# CKLink_Lite.net
KiCad netlist of a schematic drawn in Altium Designer
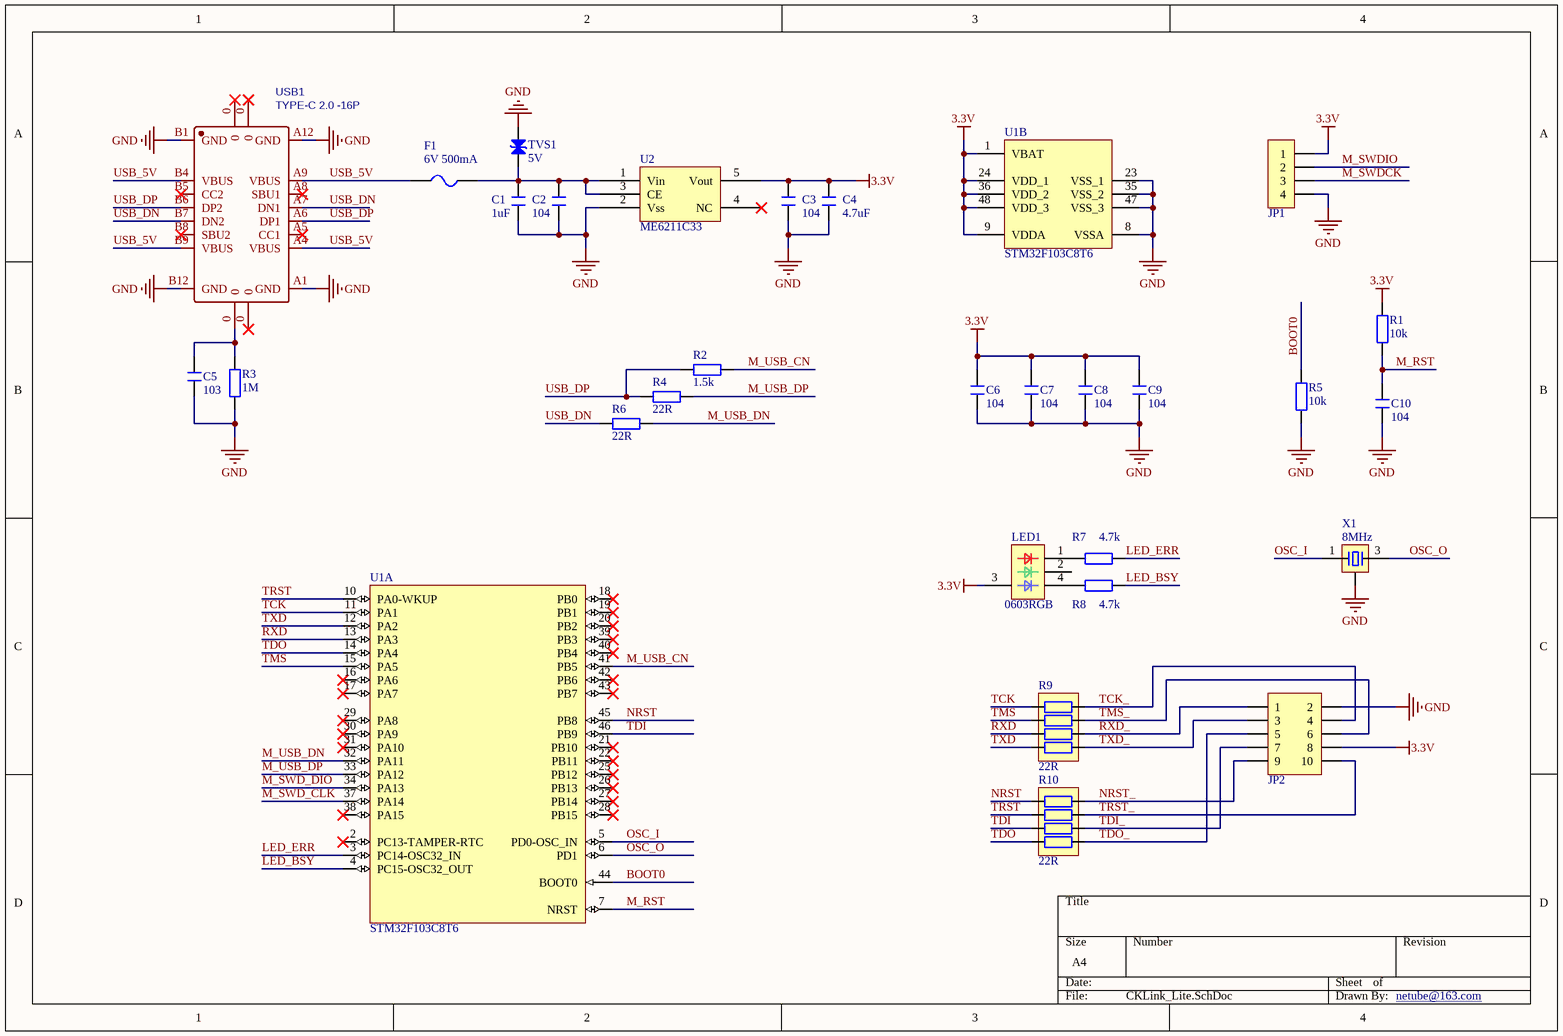
[diagram p0: CKLink_Lite.SchDoc]

(export (version "E")
  (design (tool "Eeschema 10.0.6"))
  (components
    (comp (ref "C1")
      (value "1uF")
      (footprint "C 0603_L")
      (description "贴片电容")
      (libsource (lib "0.1 - 电阻-电容-电感") (part "C"))
    )
    (comp (ref "C2")
      (value "104")
      (footprint "C 0603_L")
      (description "贴片电容")
      (libsource (lib "0.1 - 电阻-电容-电感") (part "C"))
    )
    (comp (ref "C3")
      (value "104")
      (footprint "C 0603_L")
      (description "贴片电容")
      (libsource (lib "0.1 - 电阻-电容-电感") (part "C"))
    )
    (comp (ref "C4")
      (value "4.7uF")
      (footprint "C 0603_L")
      (description "贴片电容")
      (libsource (lib "0.1 - 电阻-电容-电感") (part "C"))
    )
    (comp (ref "C5")
      (value "103")
      (footprint "C 0603_L")
      (description "贴片电容")
      (libsource (lib "0.1 - 电阻-电容-电感") (part "C"))
    )
    (comp (ref "C6")
      (value "104")
      (footprint "C 0603_L")
      (description "贴片电容")
      (libsource (lib "0.1 - 电阻-电容-电感") (part "C"))
    )
    (comp (ref "C7")
      (value "104")
      (footprint "C 0603_L")
      (description "贴片电容")
      (libsource (lib "0.1 - 电阻-电容-电感") (part "C"))
    )
    (comp (ref "C8")
      (value "104")
      (footprint "C 0603_L")
      (description "贴片电容")
      (libsource (lib "0.1 - 电阻-电容-电感") (part "C"))
    )
    (comp (ref "C9")
      (value "104")
      (footprint "C 0603_L")
      (description "贴片电容")
      (libsource (lib "0.1 - 电阻-电容-电感") (part "C"))
    )
    (comp (ref "C10")
      (value "104")
      (footprint "C 0603_L")
      (description "贴片电容")
      (libsource (lib "0.1 - 电阻-电容-电感") (part "C"))
    )
    (comp (ref "F1")
      (value "6V 500mA")
      (footprint "FU 0805")
      (description "贴片保险丝")
      (fields (field (name "版权归属") "封装库来自淘宝卖家 ID：黄晶宝石"))
      (libsource (lib "0.5 - 保险丝-晶振-光耦") (part "FU"))
    )
    (comp (ref "JP1")
      (value "HDR-1X4")
      (footprint "HDR2.54-LI-4P")
      (description "4P接插件")
      (fields (field (name "版权归属") "封装库来自淘宝 ID：黄晶宝石"))
      (libsource (lib "5.4 - 接插件-脚距2.54 (100mil) ") (part "Header 4"))
    )
    (comp (ref "JP2")
      (value "Header 5X2")
      (footprint "CHE2*5")
      (description "5*2P接插件")
      (fields (field (name "版权归属") "封装库来自淘宝 ID：黄晶宝石"))
      (libsource (lib "5.4 - 接插件-脚距2.54 (100mil) ") (part "Header 5X2"))
    )
    (comp (ref "LED1")
      (value "0603RGB")
      (footprint "0603RGB")
      (libsource (lib "0.3 - LED发光二极管") (part "0603RGB"))
    )
    (comp (ref "R1")
      (value "10k")
      (footprint "R 0603_L")
      (description "贴片电阻")
      (libsource (lib "0.1 - 电阻-电容-电感") (part "R"))
    )
    (comp (ref "R2")
      (value "1.5k")
      (footprint "R 0603_L")
      (description "贴片电阻")
      (libsource (lib "0.1 - 电阻-电容-电感") (part "R"))
    )
    (comp (ref "R3")
      (value "1M")
      (footprint "R 0603_L")
      (description "贴片电阻")
      (libsource (lib "0.1 - 电阻-电容-电感") (part "R"))
    )
    (comp (ref "R4")
      (value "22R")
      (footprint "R 0603_L")
      (description "贴片电阻")
      (libsource (lib "0.1 - 电阻-电容-电感") (part "R"))
    )
    (comp (ref "R5")
      (value "10k")
      (footprint "R 0603_L")
      (description "贴片电阻")
      (libsource (lib "0.1 - 电阻-电容-电感") (part "R"))
    )
    (comp (ref "R6")
      (value "22R")
      (footprint "R 0603_L")
      (description "贴片电阻")
      (libsource (lib "0.1 - 电阻-电容-电感") (part "R"))
    )
    (comp (ref "R7")
      (value "4.7k")
      (footprint "R 0603_L")
      (description "贴片电阻")
      (libsource (lib "0.1 - 电阻-电容-电感") (part "R"))
    )
    (comp (ref "R8")
      (value "4.7k")
      (footprint "R 0603_L")
      (description "贴片电阻")
      (libsource (lib "0.1 - 电阻-电容-电感") (part "R"))
    )
    (comp (ref "R9")
      (value "22R")
      (footprint "RCA-8P4R-0603")
      (description "贴片排阻")
      (libsource (lib "") (part "R-8P4R_1"))
    )
    (comp (ref "R10")
      (value "22R")
      (footprint "RCA-8P4R-0603")
      (description "贴片排阻")
      (libsource (lib "0.1 - 电阻-电容-电感") (part "R-8P4R"))
    )
    (comp (ref "TVS1")
      (value "5V")
      (footprint "SOD-323")
      (description "TVS保护")
      (libsource (lib "0.2 - 二极管-整流桥") (part "TVS"))
    )
    (comp (ref "U1")
      (value "STM32F103C8T6")
      (footprint "LQFP48_L")
      (libsource (lib "2.3 - STM32 F1系列单片机") (part "STM32F103C8T6"))
    )
    (comp (ref "U2")
      (value "ME6211C33")
      (footprint "SOT23-5N")
      (description "3.3V 500mA 低压差线性稳压器")
      (libsource (lib "1.1 - 电源类芯片") (part "ME6211C33"))
    )
    (comp (ref "USB1")
      (value "TYPE-C 2.0 -16P")
      (footprint "USB-TYPE-C_16PIN-MALE-TYPE-C-31-M-12")
      (description "USB2.0 Type-C 母座 16Pin")
      (libsource (lib "0.8 - 以太网-音频-USB插座") (part "USB2.0 Type-C 16Pin母座"))
    )
    (comp (ref "X1")
      (value "8MHz")
      (footprint "CSTCE 3pin")
      (description "3脚无源晶振")
      (fields (field (name "版权归属") "封装库来自淘宝卖家 ID：黄晶宝石"))
      (libsource (lib "0.5 - 保险丝-晶振-光耦") (part "XTAL-3P"))
    )
  )
  (nets
    (net (code "1") (name "/BOOT0") (class "Default")
      (node (ref "R5") (pin "2") (pinfunction "2_2") (pintype "passive"))
      (node (ref "U1") (pin "44") (pinfunction "BOOT0_44") (pintype "input"))
    )
    (net (code "2") (name "/LED_BSY") (class "Default")
      (node (ref "R8") (pin "1") (pinfunction "1_1") (pintype "passive"))
      (node (ref "U1") (pin "4") (pinfunction "PC15-OSC32_OUT_4") (pintype "bidirectional"))
    )
    (net (code "3") (name "/LED_ERR") (class "Default")
      (node (ref "R7") (pin "1") (pinfunction "1_1") (pintype "passive"))
      (node (ref "U1") (pin "3") (pinfunction "PC14-OSC32_IN_3") (pintype "bidirectional"))
    )
    (net (code "4") (name "/M_RST") (class "Default")
      (node (ref "C10") (pin "2") (pinfunction "2_2") (pintype "passive"))
      (node (ref "R1") (pin "1") (pinfunction "1_1") (pintype "passive"))
      (node (ref "U1") (pin "7") (pinfunction "NRST_7") (pintype "bidirectional"))
    )
    (net (code "5") (name "/M_SWDCK") (class "Default")
      (node (ref "JP1") (pin "3") (pinfunction "3_3") (pintype "passive"))
    )
    (net (code "6") (name "/M_SWDIO") (class "Default")
      (node (ref "JP1") (pin "2") (pinfunction "2_2") (pintype "passive"))
    )
    (net (code "7") (name "/M_SWD_CLK") (class "Default")
      (node (ref "U1") (pin "37") (pinfunction "PA14_37") (pintype "bidirectional"))
    )
    (net (code "8") (name "/M_SWD_DIO") (class "Default")
      (node (ref "U1") (pin "34") (pinfunction "PA13_34") (pintype "bidirectional"))
    )
    (net (code "9") (name "/M_USB_CN") (class "Default")
      (node (ref "R2") (pin "1") (pinfunction "1_1") (pintype "passive"))
      (node (ref "U1") (pin "41") (pinfunction "PB5_41") (pintype "bidirectional"))
    )
    (net (code "10") (name "/M_USB_DN") (class "Default")
      (node (ref "R6") (pin "1") (pinfunction "1_1") (pintype "passive"))
      (node (ref "U1") (pin "32") (pinfunction "PA11_32") (pintype "bidirectional"))
    )
    (net (code "11") (name "/M_USB_DP") (class "Default")
      (node (ref "R4") (pin "1") (pinfunction "1_1") (pintype "passive"))
      (node (ref "U1") (pin "33") (pinfunction "PA12_33") (pintype "bidirectional"))
    )
    (net (code "12") (name "/NRST") (class "Default")
      (node (ref "R10") (pin "4") (pinfunction "4_4") (pintype "passive"))
      (node (ref "U1") (pin "45") (pinfunction "PB8_45") (pintype "bidirectional"))
    )
    (net (code "13") (name "/NRST_") (class "Default")
      (node (ref "JP2") (pin "9") (pinfunction "9_9") (pintype "passive"))
      (node (ref "R10") (pin "5") (pinfunction "5_5") (pintype "passive"))
    )
    (net (code "14") (name "/OSC_I") (class "Default")
      (node (ref "U1") (pin "5") (pinfunction "PD0-OSC_IN_5") (pintype "bidirectional"))
      (node (ref "X1") (pin "1") (pinfunction "1_1") (pintype "passive"))
    )
    (net (code "15") (name "/OSC_O") (class "Default")
      (node (ref "U1") (pin "6") (pinfunction "PD1_6") (pintype "bidirectional"))
      (node (ref "X1") (pin "3") (pinfunction "3_3") (pintype "passive"))
    )
    (net (code "16") (name "/RXD") (class "Default")
      (node (ref "R9") (pin "3") (pinfunction "3_3") (pintype "passive"))
      (node (ref "U1") (pin "13") (pinfunction "PA3_13") (pintype "bidirectional"))
    )
    (net (code "17") (name "/RXD_") (class "Default")
      (node (ref "JP2") (pin "1") (pinfunction "1_1") (pintype "passive"))
      (node (ref "R9") (pin "6") (pinfunction "6_6") (pintype "passive"))
    )
    (net (code "18") (name "/TCK") (class "Default")
      (node (ref "R9") (pin "1") (pinfunction "1_1") (pintype "passive"))
      (node (ref "U1") (pin "11") (pinfunction "PA1_11") (pintype "bidirectional"))
    )
    (net (code "19") (name "/TCK_") (class "Default")
      (node (ref "JP2") (pin "4") (pinfunction "4_4") (pintype "passive"))
      (node (ref "R9") (pin "8") (pinfunction "8_8") (pintype "passive"))
    )
    (net (code "20") (name "/TDI") (class "Default")
      (node (ref "R10") (pin "2") (pinfunction "2_2") (pintype "passive"))
      (node (ref "U1") (pin "46") (pinfunction "PB9_46") (pintype "bidirectional"))
    )
    (net (code "21") (name "/TDI_") (class "Default")
      (node (ref "JP2") (pin "7") (pinfunction "7_7") (pintype "passive"))
      (node (ref "R10") (pin "7") (pinfunction "7_7") (pintype "passive"))
    )
    (net (code "22") (name "/TDO") (class "Default")
      (node (ref "R10") (pin "1") (pinfunction "1_1") (pintype "passive"))
      (node (ref "U1") (pin "14") (pinfunction "PA4_14") (pintype "bidirectional"))
    )
    (net (code "23") (name "/TDO_") (class "Default")
      (node (ref "JP2") (pin "5") (pinfunction "5_5") (pintype "passive"))
      (node (ref "R10") (pin "8") (pinfunction "8_8") (pintype "passive"))
    )
    (net (code "24") (name "/TMS") (class "Default")
      (node (ref "R9") (pin "2") (pinfunction "2_2") (pintype "passive"))
      (node (ref "U1") (pin "15") (pinfunction "PA5_15") (pintype "bidirectional"))
    )
    (net (code "25") (name "/TMS_") (class "Default")
      (node (ref "JP2") (pin "6") (pinfunction "6_6") (pintype "passive"))
      (node (ref "R9") (pin "7") (pinfunction "7_7") (pintype "passive"))
    )
    (net (code "26") (name "/TRST") (class "Default")
      (node (ref "R10") (pin "3") (pinfunction "3_3") (pintype "passive"))
      (node (ref "U1") (pin "10") (pinfunction "PA0-WKUP_10") (pintype "bidirectional"))
    )
    (net (code "27") (name "/TRST_") (class "Default")
      (node (ref "JP2") (pin "10") (pinfunction "10_10") (pintype "passive"))
      (node (ref "R10") (pin "6") (pinfunction "6_6") (pintype "passive"))
    )
    (net (code "28") (name "/TXD") (class "Default")
      (node (ref "R9") (pin "4") (pinfunction "4_4") (pintype "passive"))
      (node (ref "U1") (pin "12") (pinfunction "PA2_12") (pintype "bidirectional"))
    )
    (net (code "29") (name "/TXD_") (class "Default")
      (node (ref "JP2") (pin "3") (pinfunction "3_3") (pintype "passive"))
      (node (ref "R9") (pin "5") (pinfunction "5_5") (pintype "passive"))
    )
    (net (code "30") (name "/USB_5V") (class "Default")
      (node (ref "F1") (pin "1") (pinfunction "1_1") (pintype "passive"))
      (node (ref "USB1") (pin "A4") (pinfunction "VBUS_A4") (pintype "passive"))
      (node (ref "USB1") (pin "A9") (pinfunction "VBUS_A9") (pintype "passive"))
      (node (ref "USB1") (pin "B4") (pinfunction "VBUS_B4") (pintype "passive"))
      (node (ref "USB1") (pin "B9") (pinfunction "VBUS_B9") (pintype "passive"))
    )
    (net (code "31") (name "/USB_DN") (class "Default")
      (node (ref "R6") (pin "2") (pinfunction "2_2") (pintype "passive"))
      (node (ref "USB1") (pin "A7") (pinfunction "DN1_A7") (pintype "passive"))
      (node (ref "USB1") (pin "B7") (pinfunction "DN2_B7") (pintype "passive"))
    )
    (net (code "32") (name "/USB_DP") (class "Default")
      (node (ref "R2") (pin "2") (pinfunction "2_2") (pintype "passive"))
      (node (ref "R4") (pin "2") (pinfunction "2_2") (pintype "passive"))
      (node (ref "USB1") (pin "A6") (pinfunction "DP1_A6") (pintype "passive"))
      (node (ref "USB1") (pin "B6") (pinfunction "DP2_B6") (pintype "passive"))
    )
    (net (code "33") (name "3.3V") (class "Default")
      (node (ref "C3") (pin "2") (pinfunction "2_2") (pintype "passive"))
      (node (ref "C4") (pin "2") (pinfunction "2_2") (pintype "passive"))
      (node (ref "C6") (pin "2") (pinfunction "2_2") (pintype "passive"))
      (node (ref "C7") (pin "2") (pinfunction "2_2") (pintype "passive"))
      (node (ref "C8") (pin "2") (pinfunction "2_2") (pintype "passive"))
      (node (ref "C9") (pin "2") (pinfunction "2_2") (pintype "passive"))
      (node (ref "JP1") (pin "1") (pinfunction "1_1") (pintype "passive"))
      (node (ref "JP2") (pin "8") (pinfunction "8_8") (pintype "passive"))
      (node (ref "LED1") (pin "3") (pinfunction "VCC_3") (pintype "passive"))
      (node (ref "R1") (pin "2") (pinfunction "2_2") (pintype "passive"))
      (node (ref "U1") (pin "1") (pinfunction "VBAT_1") (pintype "power_in"))
      (node (ref "U1") (pin "24") (pinfunction "VDD_1_24") (pintype "power_in"))
      (node (ref "U1") (pin "36") (pinfunction "VDD_2_36") (pintype "power_in"))
      (node (ref "U1") (pin "48") (pinfunction "VDD_3_48") (pintype "power_in"))
      (node (ref "U1") (pin "9") (pinfunction "VDDA_9") (pintype "power_in"))
      (node (ref "U2") (pin "5") (pinfunction "Vout_5") (pintype "passive"))
    )
    (net (code "34") (name "GND") (class "Default")
      (node (ref "C1") (pin "1") (pinfunction "1_1") (pintype "passive"))
      (node (ref "C10") (pin "1") (pinfunction "1_1") (pintype "passive"))
      (node (ref "C2") (pin "1") (pinfunction "1_1") (pintype "passive"))
      (node (ref "C3") (pin "1") (pinfunction "1_1") (pintype "passive"))
      (node (ref "C4") (pin "1") (pinfunction "1_1") (pintype "passive"))
      (node (ref "C5") (pin "1") (pinfunction "1_1") (pintype "passive"))
      (node (ref "C6") (pin "1") (pinfunction "1_1") (pintype "passive"))
      (node (ref "C7") (pin "1") (pinfunction "1_1") (pintype "passive"))
      (node (ref "C8") (pin "1") (pinfunction "1_1") (pintype "passive"))
      (node (ref "C9") (pin "1") (pinfunction "1_1") (pintype "passive"))
      (node (ref "JP1") (pin "4") (pinfunction "4_4") (pintype "passive"))
      (node (ref "JP2") (pin "2") (pinfunction "2_2") (pintype "passive"))
      (node (ref "R3") (pin "1") (pinfunction "1_1") (pintype "passive"))
      (node (ref "R5") (pin "1") (pinfunction "1_1") (pintype "passive"))
      (node (ref "TVS1") (pin "2") (pinfunction "K_2") (pintype "passive"))
      (node (ref "U1") (pin "23") (pinfunction "VSS_1_23") (pintype "power_in"))
      (node (ref "U1") (pin "35") (pinfunction "VSS_2_35") (pintype "power_in"))
      (node (ref "U1") (pin "47") (pinfunction "VSS_3_47") (pintype "power_in"))
      (node (ref "U1") (pin "8") (pinfunction "VSSA_8") (pintype "power_in"))
      (node (ref "U2") (pin "2") (pinfunction "Vss_2") (pintype "passive"))
      (node (ref "USB1") (pin "A1") (pinfunction "GND_A1") (pintype "passive"))
      (node (ref "USB1") (pin "A12") (pinfunction "GND_A12") (pintype "passive"))
      (node (ref "USB1") (pin "B1") (pinfunction "GND_B1") (pintype "passive"))
      (node (ref "USB1") (pin "B12") (pinfunction "GND_B12") (pintype "passive"))
      (node (ref "X1") (pin "2") (pinfunction "2_2") (pintype "passive"))
    )
    (net (code "35") (name "Net-(C5-Pad2)") (class "Default")
      (node (ref "C5") (pin "2") (pinfunction "2_2") (pintype "passive"))
      (node (ref "R3") (pin "2") (pinfunction "2_2") (pintype "passive"))
      (node (ref "USB1") (pin "0") (pinfunction "0_0") (pintype "passive"))
    )
    (net (code "36") (name "Net-(LED1-B)") (class "Default")
      (node (ref "LED1") (pin "4") (pinfunction "B_4") (pintype "passive"))
      (node (ref "R8") (pin "2") (pinfunction "2_2") (pintype "passive"))
    )
    (net (code "37") (name "Net-(LED1-R)") (class "Default")
      (node (ref "LED1") (pin "1") (pinfunction "R_1") (pintype "passive"))
      (node (ref "R7") (pin "2") (pinfunction "2_2") (pintype "passive"))
    )
    (net (code "38") (name "Net-(TVS1-A)") (class "Default")
      (node (ref "C1") (pin "2") (pinfunction "2_2") (pintype "passive"))
      (node (ref "C2") (pin "2") (pinfunction "2_2") (pintype "passive"))
      (node (ref "F1") (pin "2") (pinfunction "2_2") (pintype "passive"))
      (node (ref "TVS1") (pin "1") (pinfunction "A_1") (pintype "passive"))
      (node (ref "U2") (pin "1") (pinfunction "Vin_1") (pintype "passive"))
      (node (ref "U2") (pin "3") (pinfunction "CE_3") (pintype "passive"))
    )
    (net (code "39") (name "unconnected-(LED1-G-Pad2)") (class "Default")
      (node (ref "LED1") (pin "2") (pinfunction "G_2") (pintype "passive"))
    )
    (net (code "40") (name "unconnected-(U1A-PA6-Pad16)") (class "Default")
      (node (ref "U1") (pin "16") (pinfunction "PA6_16") (pintype "bidirectional+no_connect"))
    )
    (net (code "41") (name "unconnected-(U1A-PA7-Pad17)") (class "Default")
      (node (ref "U1") (pin "17") (pinfunction "PA7_17") (pintype "bidirectional+no_connect"))
    )
    (net (code "42") (name "unconnected-(U1A-PA8-Pad29)") (class "Default")
      (node (ref "U1") (pin "29") (pinfunction "PA8_29") (pintype "bidirectional+no_connect"))
    )
    (net (code "43") (name "unconnected-(U1A-PA9-Pad30)") (class "Default")
      (node (ref "U1") (pin "30") (pinfunction "PA9_30") (pintype "bidirectional+no_connect"))
    )
    (net (code "44") (name "unconnected-(U1A-PA10-Pad31)") (class "Default")
      (node (ref "U1") (pin "31") (pinfunction "PA10_31") (pintype "bidirectional+no_connect"))
    )
    (net (code "45") (name "unconnected-(U1A-PA15-Pad38)") (class "Default")
      (node (ref "U1") (pin "38") (pinfunction "PA15_38") (pintype "bidirectional+no_connect"))
    )
    (net (code "46") (name "unconnected-(U1A-PB0-Pad18)") (class "Default")
      (node (ref "U1") (pin "18") (pinfunction "PB0_18") (pintype "bidirectional+no_connect"))
    )
    (net (code "47") (name "unconnected-(U1A-PB1-Pad19)") (class "Default")
      (node (ref "U1") (pin "19") (pinfunction "PB1_19") (pintype "bidirectional+no_connect"))
    )
    (net (code "48") (name "unconnected-(U1A-PB2-Pad20)") (class "Default")
      (node (ref "U1") (pin "20") (pinfunction "PB2_20") (pintype "bidirectional+no_connect"))
    )
    (net (code "49") (name "unconnected-(U1A-PB3-Pad39)") (class "Default")
      (node (ref "U1") (pin "39") (pinfunction "PB3_39") (pintype "bidirectional+no_connect"))
    )
    (net (code "50") (name "unconnected-(U1A-PB4-Pad40)") (class "Default")
      (node (ref "U1") (pin "40") (pinfunction "PB4_40") (pintype "bidirectional+no_connect"))
    )
    (net (code "51") (name "unconnected-(U1A-PB6-Pad42)") (class "Default")
      (node (ref "U1") (pin "42") (pinfunction "PB6_42") (pintype "bidirectional+no_connect"))
    )
    (net (code "52") (name "unconnected-(U1A-PB7-Pad43)") (class "Default")
      (node (ref "U1") (pin "43") (pinfunction "PB7_43") (pintype "bidirectional+no_connect"))
    )
    (net (code "53") (name "unconnected-(U1A-PB10-Pad21)") (class "Default")
      (node (ref "U1") (pin "21") (pinfunction "PB10_21") (pintype "bidirectional+no_connect"))
    )
    (net (code "54") (name "unconnected-(U1A-PB11-Pad22)") (class "Default")
      (node (ref "U1") (pin "22") (pinfunction "PB11_22") (pintype "bidirectional+no_connect"))
    )
    (net (code "55") (name "unconnected-(U1A-PB12-Pad25)") (class "Default")
      (node (ref "U1") (pin "25") (pinfunction "PB12_25") (pintype "bidirectional+no_connect"))
    )
    (net (code "56") (name "unconnected-(U1A-PB13-Pad26)") (class "Default")
      (node (ref "U1") (pin "26") (pinfunction "PB13_26") (pintype "bidirectional+no_connect"))
    )
    (net (code "57") (name "unconnected-(U1A-PB14-Pad27)") (class "Default")
      (node (ref "U1") (pin "27") (pinfunction "PB14_27") (pintype "bidirectional+no_connect"))
    )
    (net (code "58") (name "unconnected-(U1A-PB15-Pad28)") (class "Default")
      (node (ref "U1") (pin "28") (pinfunction "PB15_28") (pintype "bidirectional+no_connect"))
    )
    (net (code "59") (name "unconnected-(U1A-PC13-TAMPER-RTC-Pad2)") (class "Default")
      (node (ref "U1") (pin "2") (pinfunction "PC13-TAMPER-RTC_2") (pintype "bidirectional+no_connect"))
    )
    (net (code "60") (name "unconnected-(U2-NC-Pad4)") (class "Default")
      (node (ref "U2") (pin "4") (pinfunction "NC_4") (pintype "passive+no_connect"))
    )
    (net (code "61") (name "unconnected-(USB1-CC1-PadA5)") (class "Default")
      (node (ref "USB1") (pin "A5") (pinfunction "CC1_A5") (pintype "passive+no_connect"))
    )
    (net (code "62") (name "unconnected-(USB1-CC2-PadB5)") (class "Default")
      (node (ref "USB1") (pin "B5") (pinfunction "CC2_B5") (pintype "passive+no_connect"))
    )
    (net (code "63") (name "unconnected-(USB1-Pad0)") (class "Default")
      (node (ref "USB1") (pin "0") (pinfunction "0_0") (pintype "passive+no_connect"))
    )
    (net (code "64") (name "unconnected-(USB1-Pad0)_1") (class "Default")
      (node (ref "USB1") (pin "0") (pinfunction "0_0") (pintype "passive+no_connect"))
    )
    (net (code "65") (name "unconnected-(USB1-Pad0)_2") (class "Default")
      (node (ref "USB1") (pin "0") (pinfunction "0_0") (pintype "passive+no_connect"))
    )
    (net (code "66") (name "unconnected-(USB1-SBU1-PadA8)") (class "Default")
      (node (ref "USB1") (pin "A8") (pinfunction "SBU1_A8") (pintype "passive+no_connect"))
    )
    (net (code "67") (name "unconnected-(USB1-SBU2-PadB8)") (class "Default")
      (node (ref "USB1") (pin "B8") (pinfunction "SBU2_B8") (pintype "passive+no_connect"))
    )
  )
)
